# LAN9254_B_P2.net
KiCad netlist of a schematic drawn in Altium Designer
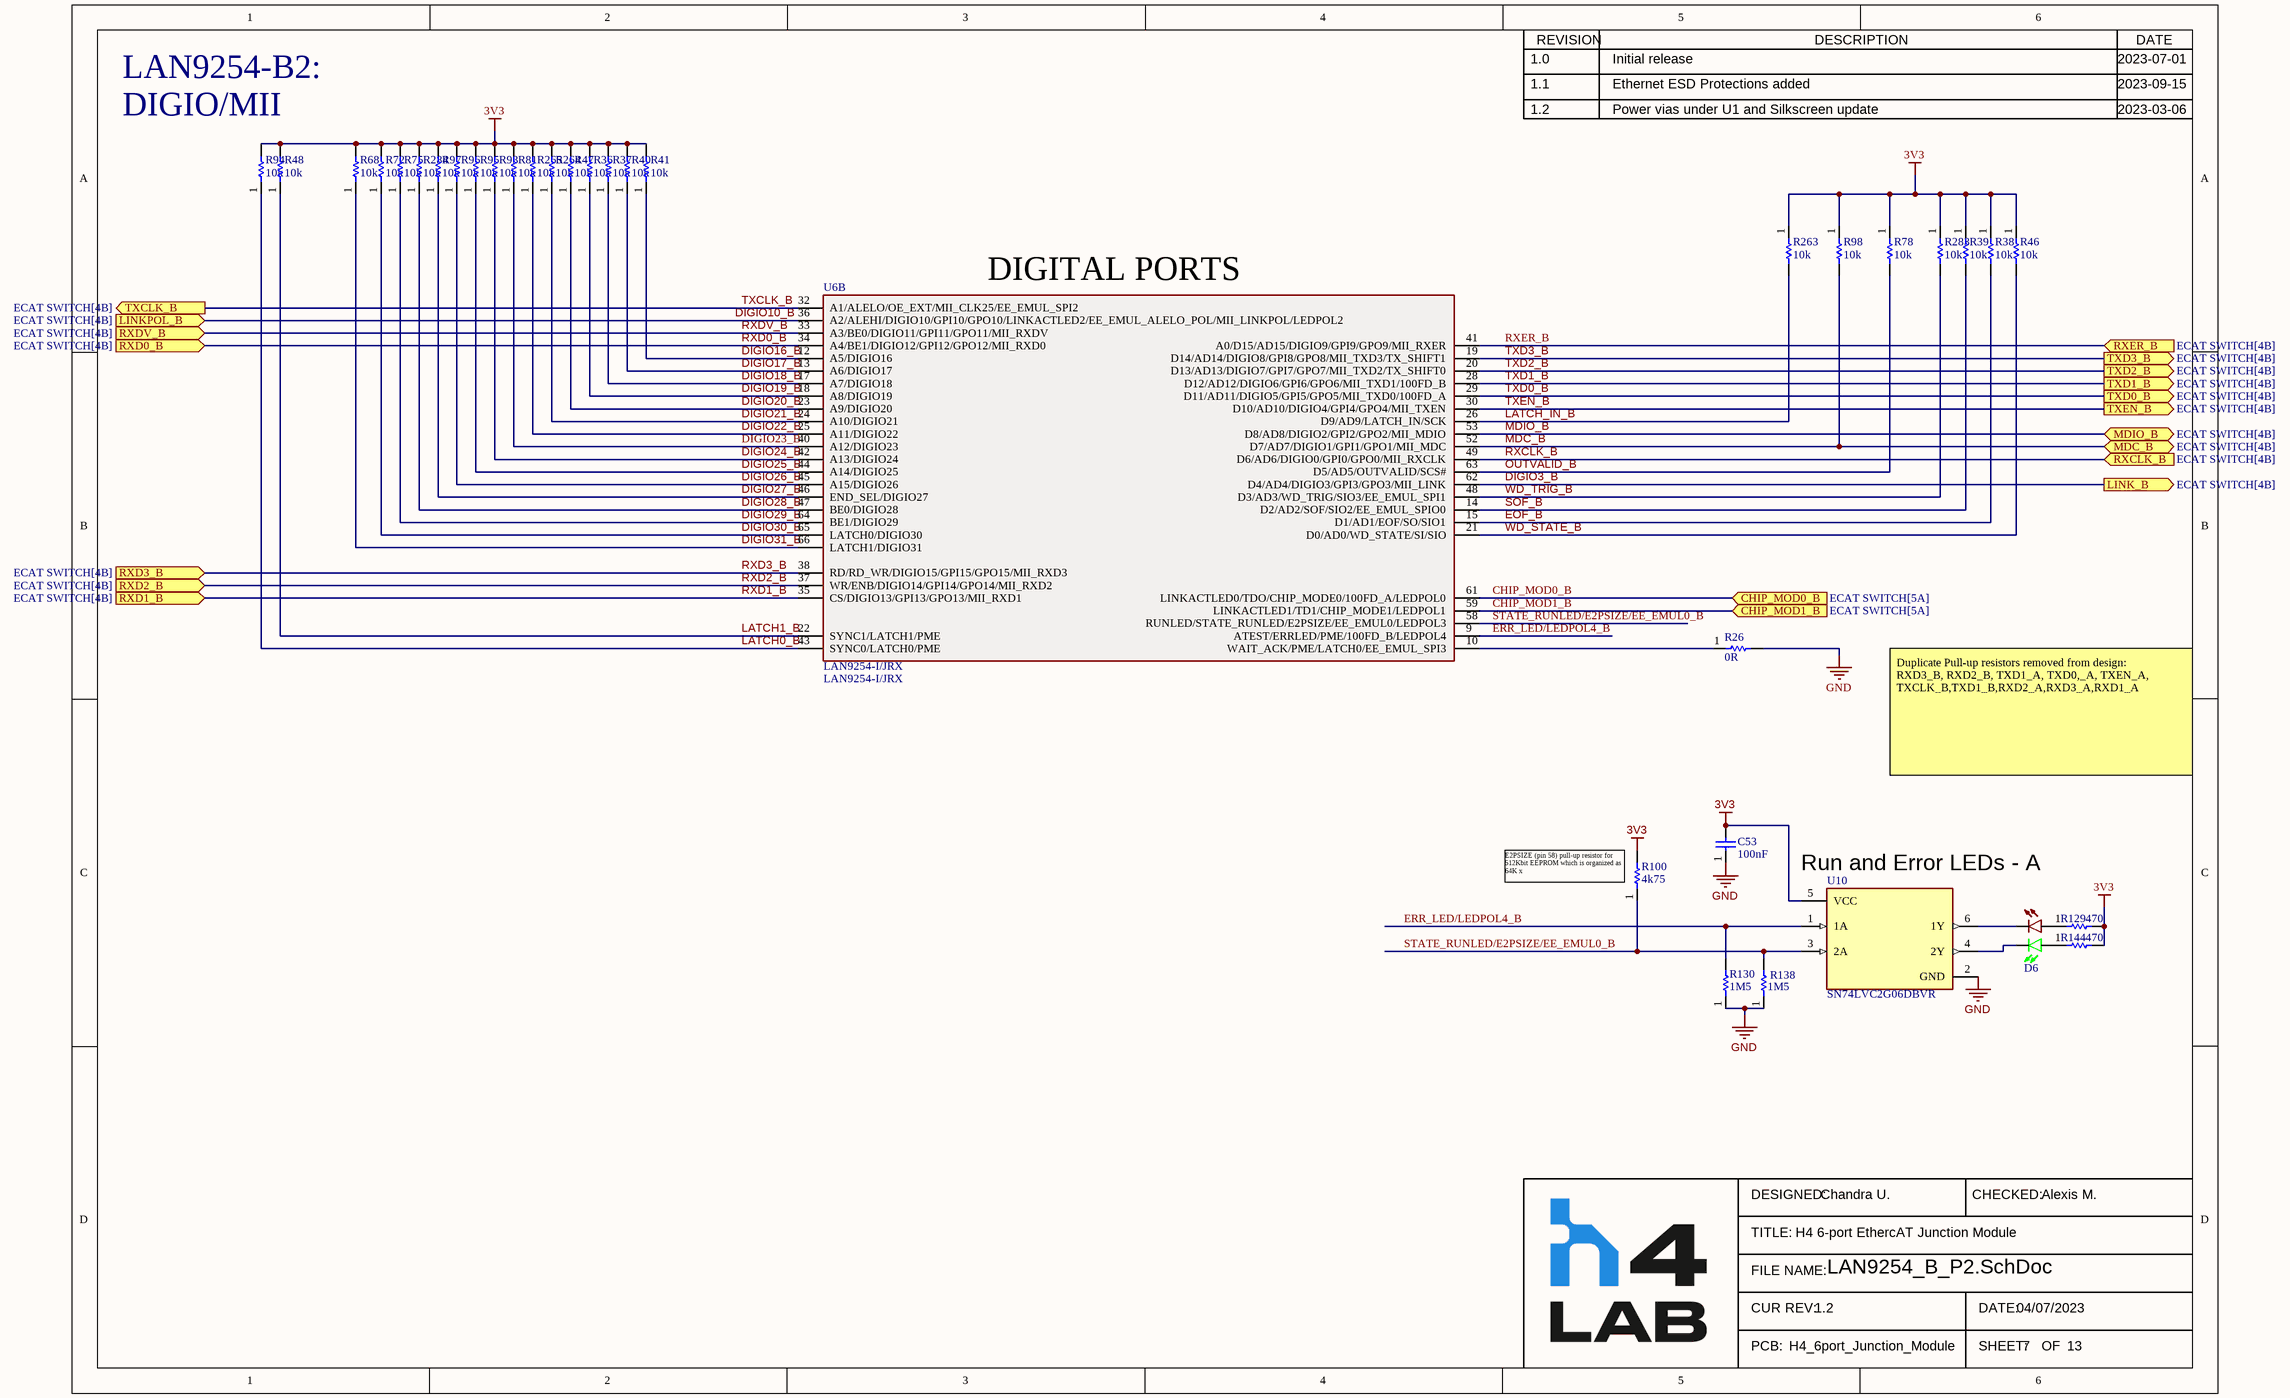
[diagram p0: LAN9254_B_P2.SchDoc]

(export (version "E")
  (design (tool "Eeschema 10.0.6"))
  (components
    (comp (ref "C53")
      (value "100nF")
      (footprint "CAPC1005X03N(0402)")
      (description "CAP CER 0.1UF 16V X7R 0402")
      (fields (field (name "MPN") "GRM155R71C104JA88D") (field (name "TOLERANCE") "5%"))
      (libsource (lib "IHMC_Altium_Lib") (part "100nF_16V_0402_CAP"))
    )
    (comp (ref "D6")
      (value "LTST-C195KGJRKT")
      (footprint "Dual_LED")
      (description "LED GREEN/RED CLEAR CHIP SMD")
      (libsource (lib "IHMC_Altium_Lib") (part "Green/Red_LED"))
    )
    (comp (ref "R26")
      (value "0R")
      (footprint "0402")
      (fields
        (field (name "MANUFACTURER") "Vishay Dale")
        (field (name "MANUFACTURER PART NUMBER") "RCS04020000Z0ED")
      )
      (libsource (lib "IHMC_Altium_Lib") (part "0R_1/5W_0402_RCS04020000Z0ED_RES"))
    )
    (comp (ref "R36")
      (value "10k")
      (footprint "RESC1005X06N(0402)")
      (description "RES SMD 10K OHM 1% 1/16W 0402")
      (fields (field (name "MPN") "RC0402FR-0710KL") (field (name "TOLERANCE") "1%"))
      (libsource (lib "IHMC_Resistors") (part "10k_1/16W_0402_RES"))
    )
    (comp (ref "R37")
      (value "10k")
      (footprint "RESC1005X06N(0402)")
      (description "RES SMD 10K OHM 1% 1/16W 0402")
      (fields (field (name "MPN") "RC0402FR-0710KL") (field (name "TOLERANCE") "1%"))
      (libsource (lib "IHMC_Resistors") (part "10k_1/16W_0402_RES"))
    )
    (comp (ref "R38")
      (value "10k")
      (footprint "RESC1005X06N(0402)")
      (description "RES SMD 10K OHM 1% 1/16W 0402")
      (fields (field (name "MPN") "RC0402FR-0710KL") (field (name "TOLERANCE") "1%"))
      (libsource (lib "IHMC_Resistors") (part "10k_1/16W_0402_RES"))
    )
    (comp (ref "R39")
      (value "10k")
      (footprint "RESC1005X06N(0402)")
      (description "RES SMD 10K OHM 1% 1/16W 0402")
      (fields (field (name "MPN") "RC0402FR-0710KL") (field (name "TOLERANCE") "1%"))
      (libsource (lib "IHMC_Resistors") (part "10k_1/16W_0402_RES"))
    )
    (comp (ref "R40")
      (value "10k")
      (footprint "RESC1005X06N(0402)")
      (description "RES SMD 10K OHM 1% 1/16W 0402")
      (fields (field (name "MPN") "RC0402FR-0710KL") (field (name "TOLERANCE") "1%"))
      (libsource (lib "IHMC_Resistors") (part "10k_1/16W_0402_RES"))
    )
    (comp (ref "R41")
      (value "10k")
      (footprint "RESC1005X06N(0402)")
      (description "RES SMD 10K OHM 1% 1/16W 0402")
      (fields (field (name "MPN") "RC0402FR-0710KL") (field (name "TOLERANCE") "1%"))
      (libsource (lib "IHMC_Resistors") (part "10k_1/16W_0402_RES"))
    )
    (comp (ref "R46")
      (value "10k")
      (footprint "RESC1005X06N(0402)")
      (description "RES SMD 10K OHM 1% 1/16W 0402")
      (fields (field (name "MPN") "RC0402FR-0710KL") (field (name "TOLERANCE") "1%"))
      (libsource (lib "IHMC_Resistors") (part "10k_1/16W_0402_RES"))
    )
    (comp (ref "R47")
      (value "10k")
      (footprint "RESC1005X06N(0402)")
      (description "RES SMD 10K OHM 1% 1/16W 0402")
      (fields (field (name "MPN") "RC0402FR-0710KL") (field (name "TOLERANCE") "1%"))
      (libsource (lib "IHMC_Resistors") (part "10k_1/16W_0402_RES"))
    )
    (comp (ref "R48")
      (value "10k")
      (footprint "RESC1005X06N(0402)")
      (description "RES SMD 10K OHM 1% 1/16W 0402")
      (fields (field (name "MPN") "RC0402FR-0710KL") (field (name "TOLERANCE") "1%"))
      (libsource (lib "IHMC_Resistors") (part "10k_1/16W_0402_RES"))
    )
    (comp (ref "R68")
      (value "10k")
      (footprint "RESC1005X06N(0402)")
      (description "RES SMD 10K OHM 1% 1/16W 0402")
      (fields (field (name "MPN") "RC0402FR-0710KL") (field (name "TOLERANCE") "1%"))
      (libsource (lib "IHMC_Resistors") (part "10k_1/16W_0402_RES"))
    )
    (comp (ref "R72")
      (value "10k")
      (footprint "RESC1005X06N(0402)")
      (description "RES SMD 10K OHM 1% 1/16W 0402")
      (fields (field (name "MPN") "RC0402FR-0710KL") (field (name "TOLERANCE") "1%"))
      (libsource (lib "IHMC_Resistors") (part "10k_1/16W_0402_RES"))
    )
    (comp (ref "R75")
      (value "10k")
      (footprint "RESC1005X06N(0402)")
      (description "RES SMD 10K OHM 1% 1/16W 0402")
      (fields (field (name "MPN") "RC0402FR-0710KL") (field (name "TOLERANCE") "1%"))
      (libsource (lib "IHMC_Resistors") (part "10k_1/16W_0402_RES"))
    )
    (comp (ref "R78")
      (value "10k")
      (footprint "RESC1005X06N(0402)")
      (description "RES SMD 10K OHM 1% 1/16W 0402")
      (fields (field (name "MPN") "RC0402FR-0710KL") (field (name "TOLERANCE") "1%"))
      (libsource (lib "IHMC_Resistors") (part "10k_1/16W_0402_RES"))
    )
    (comp (ref "R81")
      (value "10k")
      (footprint "RESC1005X06N(0402)")
      (description "RES SMD 10K OHM 1% 1/16W 0402")
      (fields (field (name "MPN") "RC0402FR-0710KL") (field (name "TOLERANCE") "1%"))
      (libsource (lib "IHMC_Resistors") (part "10k_1/16W_0402_RES"))
    )
    (comp (ref "R93")
      (value "10k")
      (footprint "RESC1005X06N(0402)")
      (description "RES SMD 10K OHM 1% 1/16W 0402")
      (fields (field (name "MPN") "RC0402FR-0710KL") (field (name "TOLERANCE") "1%"))
      (libsource (lib "IHMC_Resistors") (part "10k_1/16W_0402_RES"))
    )
    (comp (ref "R94")
      (value "10k")
      (footprint "RESC1005X06N(0402)")
      (description "RES SMD 10K OHM 1% 1/16W 0402")
      (fields (field (name "MPN") "RC0402FR-0710KL") (field (name "TOLERANCE") "1%"))
      (libsource (lib "IHMC_Resistors") (part "10k_1/16W_0402_RES"))
    )
    (comp (ref "R95")
      (value "10k")
      (footprint "RESC1005X06N(0402)")
      (description "RES SMD 10K OHM 1% 1/16W 0402")
      (fields (field (name "MPN") "RC0402FR-0710KL") (field (name "TOLERANCE") "1%"))
      (libsource (lib "IHMC_Resistors") (part "10k_1/16W_0402_RES"))
    )
    (comp (ref "R96")
      (value "10k")
      (footprint "RESC1005X06N(0402)")
      (description "RES SMD 10K OHM 1% 1/16W 0402")
      (fields (field (name "MPN") "RC0402FR-0710KL") (field (name "TOLERANCE") "1%"))
      (libsource (lib "IHMC_Resistors") (part "10k_1/16W_0402_RES"))
    )
    (comp (ref "R97")
      (value "10k")
      (footprint "RESC1005X06N(0402)")
      (description "RES SMD 10K OHM 1% 1/16W 0402")
      (fields (field (name "MPN") "RC0402FR-0710KL") (field (name "TOLERANCE") "1%"))
      (libsource (lib "IHMC_Resistors") (part "10k_1/16W_0402_RES"))
    )
    (comp (ref "R98")
      (value "10k")
      (footprint "RESC1005X06N(0402)")
      (description "RES SMD 10K OHM 1% 1/16W 0402")
      (fields (field (name "MPN") "RC0402FR-0710KL") (field (name "TOLERANCE") "1%"))
      (libsource (lib "IHMC_Resistors") (part "10k_1/16W_0402_RES"))
    )
    (comp (ref "R100")
      (value "4k75")
      (footprint "RESC1005X06N(0402)")
      (description "RES SMD 4.75K OHM 1% 1/16W 0402")
      (fields (field (name "MPN") "RC0402FR-074K75L") (field (name "POWER") "1/16"))
      (libsource (lib "IHMC_Altium_Lib") (part "4k75_1/16_0402_RES"))
    )
    (comp (ref "R129")
      (value "470")
      (footprint "0402")
      (description "Vishay CRCW Series Thick Film Resistor 0402 Case 470 5% 0.063W 200ppm/K")
      (fields
        (field (name "MANUFACTURER") "Vishay Dale")
        (field (name "MANUFACTURER PART NUMBER") "CRCW0402470RJNED")
      )
      (libsource (lib "IHMC_Altium_Lib") (part "470_1/10W_0402_CRCW0402470RJNED"))
    )
    (comp (ref "R130")
      (value "1M5")
      (footprint "0402")
      (description "RES SMD 1.5M OHM 5% 1/16W 0402")
      (fields
        (field (name "MANUFACTURER") "Vishay Dale")
        (field (name "MANUFACTURER PART NUMBER") "CRCW04021M50JNED")
      )
      (libsource (lib "IHMC_Altium_Lib") (part "1M5_1/16W_0402_CRCW04021M50JNED_RES"))
    )
    (comp (ref "R138")
      (value "1M5")
      (footprint "0402")
      (description "RES SMD 1.5M OHM 5% 1/16W 0402")
      (fields
        (field (name "MANUFACTURER") "Vishay Dale")
        (field (name "MANUFACTURER PART NUMBER") "CRCW04021M50JNED")
      )
      (libsource (lib "IHMC_Altium_Lib") (part "1M5_1/16W_0402_CRCW04021M50JNED_RES"))
    )
    (comp (ref "R144")
      (value "470")
      (footprint "0402")
      (description "Vishay CRCW Series Thick Film Resistor 0402 Case 470 5% 0.063W 200ppm/K")
      (fields
        (field (name "MANUFACTURER") "Vishay Dale")
        (field (name "MANUFACTURER PART NUMBER") "CRCW0402470RJNED")
      )
      (libsource (lib "IHMC_Altium_Lib") (part "470_1/10W_0402_CRCW0402470RJNED"))
    )
    (comp (ref "R263")
      (value "10k")
      (footprint "RESC1005X06N(0402)")
      (description "RES SMD 10K OHM 1% 1/16W 0402")
      (fields (field (name "MPN") "RC0402FR-0710KL") (field (name "TOLERANCE") "1%"))
      (libsource (lib "IHMC_Resistors") (part "10k_1/16W_0402_RES"))
    )
    (comp (ref "R264")
      (value "10k")
      (footprint "RESC1005X06N(0402)")
      (description "RES SMD 10K OHM 1% 1/16W 0402")
      (fields (field (name "MPN") "RC0402FR-0710KL") (field (name "TOLERANCE") "1%"))
      (libsource (lib "IHMC_Resistors") (part "10k_1/16W_0402_RES"))
    )
    (comp (ref "R265")
      (value "10k")
      (footprint "RESC1005X06N(0402)")
      (description "RES SMD 10K OHM 1% 1/16W 0402")
      (fields (field (name "MPN") "RC0402FR-0710KL") (field (name "TOLERANCE") "1%"))
      (libsource (lib "IHMC_Resistors") (part "10k_1/16W_0402_RES"))
    )
    (comp (ref "R283")
      (value "10k")
      (footprint "RESC1005X06N(0402)")
      (description "RES SMD 10K OHM 1% 1/16W 0402")
      (fields (field (name "MPN") "RC0402FR-0710KL") (field (name "TOLERANCE") "1%"))
      (libsource (lib "IHMC_Resistors") (part "10k_1/16W_0402_RES"))
    )
    (comp (ref "R284")
      (value "10k")
      (footprint "RESC1005X06N(0402)")
      (description "RES SMD 10K OHM 1% 1/16W 0402")
      (fields (field (name "MPN") "RC0402FR-0710KL") (field (name "TOLERANCE") "1%"))
      (libsource (lib "IHMC_Resistors") (part "10k_1/16W_0402_RES"))
    )
    (comp (ref "U6")
      (value "LAN9254-I/JRX")
      (footprint "QFP50P1400X1400X120-81N")
      (description "2/3-PORT Ethercat Slave Controller With 32 Digios With Integrated Ethernet Phys")
      (fields (field (name "MANUFACTURER") "Microchip"))
      (libsource (lib "IHMC_Ethernet") (part "LAN9254-I/JRX"))
    )
    (comp (ref "U10")
      (value "SN74LVC2G06DBVR")
      (footprint "FP-DBV0006A-IPC_C")
      (description "Buffer/Driver 2-CH Inverting Open Drain CMOS 6-Pin SOT-23 T/R")
      (fields (field (name "MANUFACTURER") "Texas Instruments"))
      (libsource (lib "IHMC_Altium_Lib") (part "BUF_dual_SN74LVC2G06DBVR"))
    )
  )
  (nets
    (net (code "1") (name "/CHIP_MOD0_B") (class "Default")
      (node (ref "U6") (pin "61") (pinfunction "LINKACTLED0/TDO/CHIP_MODE0/100FD_A/LEDPOL0_61") (pintype "passive"))
    )
    (net (code "2") (name "/CHIP_MOD1_B") (class "Default")
      (node (ref "U6") (pin "59") (pinfunction "LINKACTLED1/TD1/CHIP_MODE1/LEDPOL1_59") (pintype "passive"))
    )
    (net (code "3") (name "/DIGIO3_B") (class "Default")
      (node (ref "U6") (pin "62") (pinfunction "D4/AD4/DIGIO3/GPI3/GPO3/MII_LINK_62") (pintype "passive"))
    )
    (net (code "4") (name "/DIGIO10_B") (class "Default")
      (node (ref "U6") (pin "36") (pinfunction "A2/ALEHI/DIGIO10/GPI10/GPO10/LINKACTLED2/EE_EMUL_ALELO_POL/MII_LINKPOL/LEDPOL2_36") (pintype "passive"))
    )
    (net (code "5") (name "/DIGIO16_B") (class "Default")
      (node (ref "R41") (pin "1") (pinfunction "1_1") (pintype "passive"))
      (node (ref "U6") (pin "12") (pinfunction "A5/DIGIO16_12") (pintype "passive"))
    )
    (net (code "6") (name "/DIGIO17_B") (class "Default")
      (node (ref "R40") (pin "1") (pinfunction "1_1") (pintype "passive"))
      (node (ref "U6") (pin "13") (pinfunction "A6/DIGIO17_13") (pintype "passive"))
    )
    (net (code "7") (name "/DIGIO18_B") (class "Default")
      (node (ref "R37") (pin "1") (pinfunction "1_1") (pintype "passive"))
      (node (ref "U6") (pin "17") (pinfunction "A7/DIGIO18_17") (pintype "passive"))
    )
    (net (code "8") (name "/DIGIO19_B") (class "Default")
      (node (ref "R36") (pin "1") (pinfunction "1_1") (pintype "passive"))
      (node (ref "U6") (pin "18") (pinfunction "A8/DIGIO19_18") (pintype "passive"))
    )
    (net (code "9") (name "/DIGIO20_B") (class "Default")
      (node (ref "R47") (pin "1") (pinfunction "1_1") (pintype "passive"))
      (node (ref "U6") (pin "23") (pinfunction "A9/DIGIO20_23") (pintype "passive"))
    )
    (net (code "10") (name "/DIGIO21_B") (class "Default")
      (node (ref "R264") (pin "1") (pinfunction "1_1") (pintype "passive"))
      (node (ref "U6") (pin "24") (pinfunction "A10/DIGIO21_24") (pintype "passive"))
    )
    (net (code "11") (name "/DIGIO22_B") (class "Default")
      (node (ref "R265") (pin "1") (pinfunction "1_1") (pintype "passive"))
      (node (ref "U6") (pin "25") (pinfunction "A11/DIGIO22_25") (pintype "passive"))
    )
    (net (code "12") (name "/DIGIO23_B") (class "Default")
      (node (ref "R81") (pin "1") (pinfunction "1_1") (pintype "passive"))
      (node (ref "U6") (pin "40") (pinfunction "A12/DIGIO23_40") (pintype "passive"))
    )
    (net (code "13") (name "/DIGIO24_B") (class "Default")
      (node (ref "R93") (pin "1") (pinfunction "1_1") (pintype "passive"))
      (node (ref "U6") (pin "42") (pinfunction "A13/DIGIO24_42") (pintype "passive"))
    )
    (net (code "14") (name "/DIGIO25_B") (class "Default")
      (node (ref "R95") (pin "1") (pinfunction "1_1") (pintype "passive"))
      (node (ref "U6") (pin "44") (pinfunction "A14/DIGIO25_44") (pintype "passive"))
    )
    (net (code "15") (name "/DIGIO26_B") (class "Default")
      (node (ref "R96") (pin "1") (pinfunction "1_1") (pintype "passive"))
      (node (ref "U6") (pin "45") (pinfunction "A15/DIGIO26_45") (pintype "passive"))
    )
    (net (code "16") (name "/DIGIO27_B") (class "Default")
      (node (ref "R97") (pin "1") (pinfunction "1_1") (pintype "passive"))
      (node (ref "U6") (pin "46") (pinfunction "END_SEL/DIGIO27_46") (pintype "passive"))
    )
    (net (code "17") (name "/DIGIO28_B") (class "Default")
      (node (ref "R284") (pin "1") (pinfunction "1_1") (pintype "passive"))
      (node (ref "U6") (pin "47") (pinfunction "BE0/DIGIO28_47") (pintype "passive"))
    )
    (net (code "18") (name "/DIGIO29_B") (class "Default")
      (node (ref "R75") (pin "1") (pinfunction "1_1") (pintype "passive"))
      (node (ref "U6") (pin "64") (pinfunction "BE1/DIGIO29_64") (pintype "passive"))
    )
    (net (code "19") (name "/DIGIO30_B") (class "Default")
      (node (ref "R72") (pin "1") (pinfunction "1_1") (pintype "passive"))
      (node (ref "U6") (pin "65") (pinfunction "LATCH0/DIGIO30_65") (pintype "passive"))
    )
    (net (code "20") (name "/DIGIO31_B") (class "Default")
      (node (ref "R68") (pin "1") (pinfunction "1_1") (pintype "passive"))
      (node (ref "U6") (pin "66") (pinfunction "LATCH1/DIGIO31_66") (pintype "passive"))
    )
    (net (code "21") (name "/EOF_B") (class "Default")
      (node (ref "R38") (pin "2") (pinfunction "2_2") (pintype "passive"))
      (node (ref "U6") (pin "15") (pinfunction "D1/AD1/EOF/SO/SIO1_15") (pintype "passive"))
    )
    (net (code "22") (name "/ERR_LED{slash}LEDPOL4_B") (class "Default")
      (node (ref "R130") (pin "2") (pinfunction "2_2") (pintype "passive"))
      (node (ref "U10") (pin "1") (pinfunction "1A_1") (pintype "input"))
      (node (ref "U6") (pin "9") (pinfunction "ATEST/ERRLED/PME/100FD_B/LEDPOL4_9") (pintype "passive"))
    )
    (net (code "23") (name "/LATCH0_B") (class "Default")
      (node (ref "R94") (pin "1") (pinfunction "1_1") (pintype "passive"))
      (node (ref "U6") (pin "43") (pinfunction "SYNC0/LATCH0/PME_43") (pintype "passive"))
    )
    (net (code "24") (name "/LATCH1_B") (class "Default")
      (node (ref "R48") (pin "1") (pinfunction "1_1") (pintype "passive"))
      (node (ref "U6") (pin "22") (pinfunction "SYNC1/LATCH1/PME_22") (pintype "passive"))
    )
    (net (code "25") (name "/LATCH_IN_B") (class "Default")
      (node (ref "R263") (pin "2") (pinfunction "2_2") (pintype "passive"))
      (node (ref "U6") (pin "26") (pinfunction "D9/AD9/LATCH_IN/SCK_26") (pintype "passive"))
    )
    (net (code "26") (name "/MDC_B") (class "Default")
      (node (ref "R98") (pin "2") (pinfunction "2_2") (pintype "passive"))
      (node (ref "U6") (pin "52") (pinfunction "D7/AD7/DIGIO1/GPI1/GPO1/MII_MDC_52") (pintype "passive"))
    )
    (net (code "27") (name "/MDIO_B") (class "Default")
      (node (ref "U6") (pin "53") (pinfunction "D8/AD8/DIGIO2/GPI2/GPO2/MII_MDIO_53") (pintype "passive"))
    )
    (net (code "28") (name "/OUTVALID_B") (class "Default")
      (node (ref "R78") (pin "2") (pinfunction "2_2") (pintype "passive"))
      (node (ref "U6") (pin "63") (pinfunction "D5/AD5/OUTVALID/SCS#_63") (pintype "passive"))
    )
    (net (code "29") (name "/RXCLK_B") (class "Default")
      (node (ref "U6") (pin "49") (pinfunction "D6/AD6/DIGIO0/GPI0/GPO0/MII_RXCLK_49") (pintype "passive"))
    )
    (net (code "30") (name "/RXD0_B") (class "Default")
      (node (ref "U6") (pin "34") (pinfunction "A4/BE1/DIGIO12/GPI12/GPO12/MII_RXD0_34") (pintype "passive"))
    )
    (net (code "31") (name "/RXD1_B") (class "Default")
      (node (ref "U6") (pin "35") (pinfunction "CS/DIGIO13/GPI13/GPO13/MII_RXD1_35") (pintype "passive"))
    )
    (net (code "32") (name "/RXD2_B") (class "Default")
      (node (ref "U6") (pin "37") (pinfunction "WR/ENB/DIGIO14/GPI14/GPO14/MII_RXD2_37") (pintype "passive"))
    )
    (net (code "33") (name "/RXD3_B") (class "Default")
      (node (ref "U6") (pin "38") (pinfunction "RD/RD_WR/DIGIO15/GPI15/GPO15/MII_RXD3_38") (pintype "passive"))
    )
    (net (code "34") (name "/RXDV_B") (class "Default")
      (node (ref "U6") (pin "33") (pinfunction "A3/BE0/DIGIO11/GPI11/GPO11/MII_RXDV_33") (pintype "passive"))
    )
    (net (code "35") (name "/RXER_B") (class "Default")
      (node (ref "U6") (pin "41") (pinfunction "A0/D15/AD15/DIGIO9/GPI9/GPO9/MII_RXER_41") (pintype "passive"))
    )
    (net (code "36") (name "/SOF_B") (class "Default")
      (node (ref "R39") (pin "2") (pinfunction "2_2") (pintype "passive"))
      (node (ref "U6") (pin "14") (pinfunction "D2/AD2/SOF/SIO2/EE_EMUL_SPIO0_14") (pintype "passive"))
    )
    (net (code "37") (name "/STATE_RUNLED{slash}E2PSIZE{slash}EE_EMUL0_B") (class "Default")
      (node (ref "R100") (pin "1") (pinfunction "1_1") (pintype "passive"))
      (node (ref "R138") (pin "2") (pinfunction "2_2") (pintype "passive"))
      (node (ref "U10") (pin "3") (pinfunction "2A_3") (pintype "input"))
      (node (ref "U6") (pin "58") (pinfunction "RUNLED/STATE_RUNLED/E2PSIZE/EE_EMUL0/LEDPOL3_58") (pintype "passive"))
    )
    (net (code "38") (name "/TXCLK_B") (class "Default")
      (node (ref "U6") (pin "32") (pinfunction "A1/ALELO/OE_EXT/MII_CLK25/EE_EMUL_SPI2_32") (pintype "passive"))
    )
    (net (code "39") (name "/TXD0_B") (class "Default")
      (node (ref "U6") (pin "29") (pinfunction "D11/AD11/DIGIO5/GPI5/GPO5/MII_TXD0/100FD_A_29") (pintype "passive"))
    )
    (net (code "40") (name "/TXD1_B") (class "Default")
      (node (ref "U6") (pin "28") (pinfunction "D12/AD12/DIGIO6/GPI6/GPO6/MII_TXD1/100FD_B_28") (pintype "passive"))
    )
    (net (code "41") (name "/TXD2_B") (class "Default")
      (node (ref "U6") (pin "20") (pinfunction "D13/AD13/DIGIO7/GPI7/GPO7/MII_TXD2/TX_SHIFT0_20") (pintype "passive"))
    )
    (net (code "42") (name "/TXD3_B") (class "Default")
      (node (ref "U6") (pin "19") (pinfunction "D14/AD14/DIGIO8/GPI8/GPO8/MII_TXD3/TX_SHIFT1_19") (pintype "passive"))
    )
    (net (code "43") (name "/TXEN_B") (class "Default")
      (node (ref "U6") (pin "30") (pinfunction "D10/AD10/DIGIO4/GPI4/GPO4/MII_TXEN_30") (pintype "passive"))
    )
    (net (code "44") (name "/WD_STATE_B") (class "Default")
      (node (ref "R46") (pin "2") (pinfunction "2_2") (pintype "passive"))
      (node (ref "U6") (pin "21") (pinfunction "D0/AD0/WD_STATE/SI/SIO_21") (pintype "passive"))
    )
    (net (code "45") (name "/WD_TRIG_B") (class "Default")
      (node (ref "R283") (pin "2") (pinfunction "2_2") (pintype "passive"))
      (node (ref "U6") (pin "48") (pinfunction "D3/AD3/WD_TRIG/SIO3/EE_EMUL_SPI1_48") (pintype "passive"))
    )
    (net (code "46") (name "3V3") (class "Default")
      (node (ref "C53") (pin "2") (pinfunction "2_2") (pintype "passive"))
      (node (ref "R100") (pin "2") (pinfunction "2_2") (pintype "passive"))
      (node (ref "R129") (pin "2") (pinfunction "2_2") (pintype "passive"))
      (node (ref "R144") (pin "2") (pinfunction "2_2") (pintype "passive"))
      (node (ref "R263") (pin "1") (pinfunction "1_1") (pintype "passive"))
      (node (ref "R264") (pin "2") (pinfunction "2_2") (pintype "passive"))
      (node (ref "R265") (pin "2") (pinfunction "2_2") (pintype "passive"))
      (node (ref "R283") (pin "1") (pinfunction "1_1") (pintype "passive"))
      (node (ref "R284") (pin "2") (pinfunction "2_2") (pintype "passive"))
      (node (ref "R36") (pin "2") (pinfunction "2_2") (pintype "passive"))
      (node (ref "R37") (pin "2") (pinfunction "2_2") (pintype "passive"))
      (node (ref "R38") (pin "1") (pinfunction "1_1") (pintype "passive"))
      (node (ref "R39") (pin "1") (pinfunction "1_1") (pintype "passive"))
      (node (ref "R40") (pin "2") (pinfunction "2_2") (pintype "passive"))
      (node (ref "R41") (pin "2") (pinfunction "2_2") (pintype "passive"))
      (node (ref "R46") (pin "1") (pinfunction "1_1") (pintype "passive"))
      (node (ref "R47") (pin "2") (pinfunction "2_2") (pintype "passive"))
      (node (ref "R48") (pin "2") (pinfunction "2_2") (pintype "passive"))
      (node (ref "R68") (pin "2") (pinfunction "2_2") (pintype "passive"))
      (node (ref "R72") (pin "2") (pinfunction "2_2") (pintype "passive"))
      (node (ref "R75") (pin "2") (pinfunction "2_2") (pintype "passive"))
      (node (ref "R78") (pin "1") (pinfunction "1_1") (pintype "passive"))
      (node (ref "R81") (pin "2") (pinfunction "2_2") (pintype "passive"))
      (node (ref "R93") (pin "2") (pinfunction "2_2") (pintype "passive"))
      (node (ref "R94") (pin "2") (pinfunction "2_2") (pintype "passive"))
      (node (ref "R95") (pin "2") (pinfunction "2_2") (pintype "passive"))
      (node (ref "R96") (pin "2") (pinfunction "2_2") (pintype "passive"))
      (node (ref "R97") (pin "2") (pinfunction "2_2") (pintype "passive"))
      (node (ref "R98") (pin "1") (pinfunction "1_1") (pintype "passive"))
      (node (ref "U10") (pin "5") (pinfunction "VCC_5") (pintype "power_in"))
    )
    (net (code "47") (name "GND") (class "Default")
      (node (ref "C53") (pin "1") (pinfunction "1_1") (pintype "passive"))
      (node (ref "R130") (pin "1") (pinfunction "1_1") (pintype "passive"))
      (node (ref "R138") (pin "1") (pinfunction "1_1") (pintype "passive"))
      (node (ref "R26") (pin "2") (pinfunction "2_2") (pintype "passive"))
      (node (ref "U10") (pin "2") (pinfunction "GND_2") (pintype "power_in"))
    )
    (net (code "48") (name "Net-(D6-Pad1)") (class "Default")
      (node (ref "D6") (pin "1") (pinfunction "1_1") (pintype "passive"))
      (node (ref "R144") (pin "1") (pinfunction "1_1") (pintype "passive"))
    )
    (net (code "49") (name "Net-(D6-Pad2)") (class "Default")
      (node (ref "D6") (pin "2") (pinfunction "2_2") (pintype "passive"))
      (node (ref "R129") (pin "1") (pinfunction "1_1") (pintype "passive"))
    )
    (net (code "50") (name "Net-(U6B-WAIT_ACK{slash}PME{slash}LATCH0{slash}EE_EMUL_SPI3)") (class "Default")
      (node (ref "R26") (pin "1") (pinfunction "1_1") (pintype "passive"))
      (node (ref "U6") (pin "10") (pinfunction "WAIT_ACK/PME/LATCH0/EE_EMUL_SPI3_10") (pintype "passive"))
    )
    (net (code "51") (name "Net-(U10-1Y)") (class "Default")
      (node (ref "D6") (pin "4") (pinfunction "4_4") (pintype "passive"))
      (node (ref "U10") (pin "6") (pinfunction "1Y_6") (pintype "output"))
    )
    (net (code "52") (name "Net-(U10-2Y)") (class "Default")
      (node (ref "D6") (pin "3") (pinfunction "3_3") (pintype "passive"))
      (node (ref "U10") (pin "4") (pinfunction "2Y_4") (pintype "output"))
    )
  )
)
